# ESP32_Module.net
KiCad netlist of a schematic drawn in Altium Designer
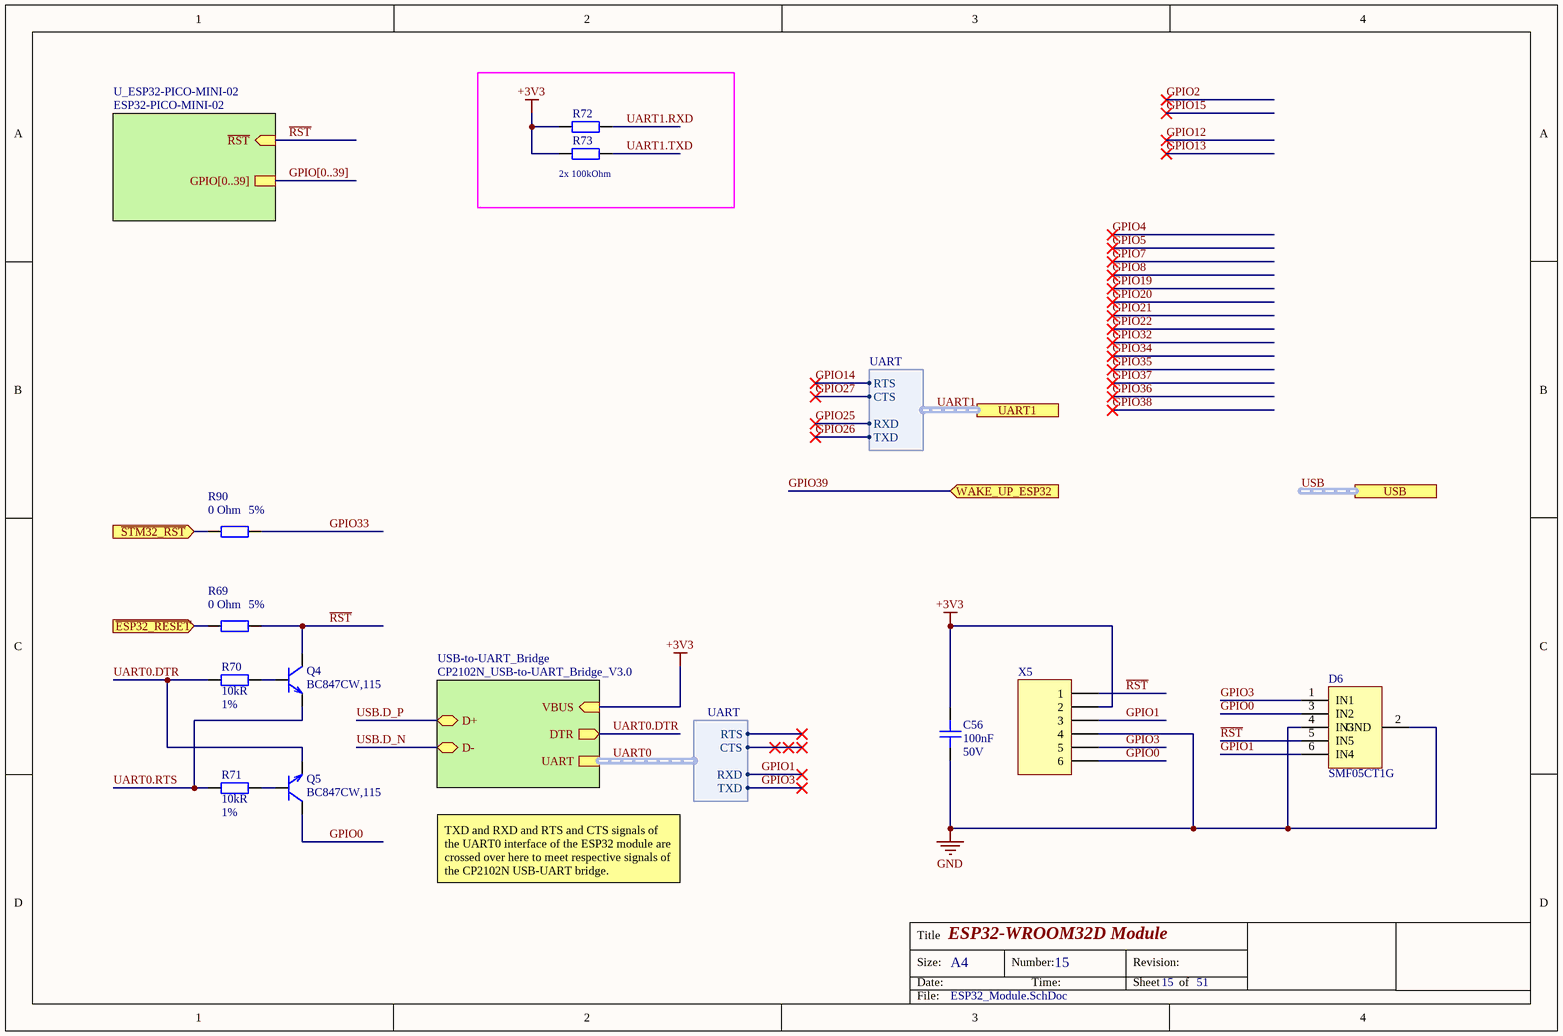
[diagram p0: ESP32_Module.SchDoc]

(export (version "E")
  (design (tool "Eeschema 10.0.6"))
  (components
    (comp (ref "C56")
      (value "CAP CER 0.1UF 50V X7R 0402")
      (footprint "C0402")
      (description "0.1µF ±10% 50V Ceramic Capacitor X7R 0402 (1005 Metric)")
      (fields
        (field (name "MANUFACTURER") "TDK")
        (field (name "MANUFACTURER PART NUMBER") "CGA2B3X7R1H104K050BB")
        (field (name "CAPACITANCE") "100nF")
        (field (name "VOLTAGE") "50V")
      )
      (libsource (lib "capacitors_smd") (part "CAP CER 0.1UF 50V X7R 0402"))
    )
    (comp (ref "D6")
      (value "SMF05CT1G")
      (footprint "SOT363_SOP65P210X265-6N")
      (description "12.5V Clamp 8A (8/20µs) Ipp Tvs Diode Surface Mount SC-88/SC70-6/SOT-363")
      (fields (field (name "MANUFACTURER") "ON Semiconductor"))
      (libsource (lib "diodes_tvs") (part "TVS DIODE 5V 12.5V 5CH SC88"))
    )
    (comp (ref "Q4")
      (value "BC847CW,115")
      (footprint "SOT-323")
      (description "Bipolar (BJT) Transistor NPN 45V 100mA 100MHz 200mW Surface Mount SOT-323-3")
      (fields (field (name "MANUFACTURER") "Nexperia"))
      (libsource (lib "bipolar-junction_transistors") (part "TRANS BC847CW,115 NPN 45V 0.1A SOT323"))
    )
    (comp (ref "Q5")
      (value "BC847CW,115")
      (footprint "SOT-323")
      (description "Bipolar (BJT) Transistor NPN 45V 100mA 100MHz 200mW Surface Mount SOT-323-3")
      (fields (field (name "MANUFACTURER") "Nexperia"))
      (libsource (lib "bipolar-junction_transistors") (part "TRANS BC847CW,115 NPN 45V 0.1A SOT323"))
    )
    (comp (ref "R69")
      (value "RES SMD 0 OHM JUMPER 1/16W 0402")
      (footprint "R0402")
      (description "0 Ohms Jumper 0.063W, 1/16W Chip Resistor 0402 (1005 Metric) Moisture Resistant Thick Film")
      (fields
        (field (name "MANUFACTURER") "Yageo")
        (field (name "MANUFACTURER PART NUMBER") "RC0402JR-070RL")
        (field (name "TOLERANCE") "5%")
        (field (name "RESISTANCE") "0 Ohm")
      )
      (libsource (lib "resistors_smd") (part "RES SMD 0 OHM JUMPER 1/16W 0402"))
    )
    (comp (ref "R70")
      (value "RES SMD 10K OHM 1% 1/16W 0402")
      (footprint "R0402")
      (description "10 kOhms ±1% 0.063W, 1/16W Chip Resistor 0402 (1005 Metric) Moisture Resistant Thick Film")
      (fields
        (field (name "MANUFACTURER PART NUMBER") "RC0402FR-0710KP")
        (field (name "MANUFACTURER") "Yageo")
        (field (name "RESISTANCE") "10kR")
        (field (name "TOLERANCE") "1%")
      )
      (libsource (lib "resistors_smd") (part "RES SMD 10K OHM 1% 1/16W 0402"))
    )
    (comp (ref "R71")
      (value "RES SMD 10K OHM 1% 1/16W 0402")
      (footprint "R0402")
      (description "10 kOhms ±1% 0.063W, 1/16W Chip Resistor 0402 (1005 Metric) Moisture Resistant Thick Film")
      (fields
        (field (name "MANUFACTURER PART NUMBER") "RC0402FR-0710KP")
        (field (name "MANUFACTURER") "Yageo")
        (field (name "RESISTANCE") "10kR")
        (field (name "TOLERANCE") "1%")
      )
      (libsource (lib "resistors_smd") (part "RES SMD 10K OHM 1% 1/16W 0402"))
    )
    (comp (ref "R72")
      (value "RES SMD 100K OHM 1% 1/16W 0402")
      (footprint "R0402")
      (description "100 kOhms ±1% 0.063W, 1/16W Chip Resistor 0402 (1005 Metric) Moisture Resistant Thick Film")
      (fields
        (field (name "MANUFACTURER") "Yageo")
        (field (name "MANUFACTURER PART NUMBER") "RC0402FR-07100KL")
      )
      (libsource (lib "resistors_smd") (part "RES SMD 100K OHM 1% 1/16W 0402"))
    )
    (comp (ref "R73")
      (value "RES SMD 100K OHM 1% 1/16W 0402")
      (footprint "R0402")
      (description "100 kOhms ±1% 0.063W, 1/16W Chip Resistor 0402 (1005 Metric) Moisture Resistant Thick Film")
      (fields
        (field (name "MANUFACTURER") "Yageo")
        (field (name "MANUFACTURER PART NUMBER") "RC0402FR-07100KL")
      )
      (libsource (lib "resistors_smd") (part "RES SMD 100K OHM 1% 1/16W 0402"))
    )
    (comp (ref "R90")
      (value "RES SMD 0 OHM JUMPER 1/16W 0402")
      (footprint "R0402")
      (description "0 Ohms Jumper 0.063W, 1/16W Chip Resistor 0402 (1005 Metric) Moisture Resistant Thick Film")
      (fields
        (field (name "MANUFACTURER") "Yageo")
        (field (name "MANUFACTURER PART NUMBER") "RC0402JR-070RL")
        (field (name "TOLERANCE") "5%")
        (field (name "RESISTANCE") "0 Ohm")
      )
      (libsource (lib "resistors_smd") (part "RES SMD 0 OHM JUMPER 1/16W 0402"))
    )
    (comp (ref "X5")
      (value "~")
      (footprint "TC2030-IDC-NL")
      (description "Tag-Connect TC2030-MCP-NL (3x2 pins No Legs)")
      (fields
        (field (name "MANUFACTURER") "Tag-Connect LLC")
        (field (name "MANUFACTURER PART NUMBER") "TC2030-IDC-NL")
      )
      (libsource (lib "EvansWerks") (part "TC2030-IDC-NL"))
    )
  )
  (nets
    (net (code "17") (name "+3V3") (class "Default")
      (node (ref "C56") (pin "2") (pinfunction "2_2") (pintype "passive"))
      (node (ref "R72") (pin "1") (pinfunction "1_1") (pintype "passive"))
      (node (ref "R73") (pin "1") (pinfunction "1_1") (pintype "passive"))
      (node (ref "X5") (pin "2") (pinfunction "2_2") (pintype "passive"))
    )
    (net (code "18") (name "/ESP32_RESET") (class "Default")
      (node (ref "R69") (pin "1") (pinfunction "1_1") (pintype "passive"))
    )
    (net (code "19") (name "/GPIO0") (class "Default")
      (node (ref "D6") (pin "3") (pinfunction "IN2_3") (pintype "passive"))
      (node (ref "Q5") (pin "3") (pinfunction "C_3") (pintype "passive"))
      (node (ref "X5") (pin "6") (pinfunction "6_6") (pintype "passive"))
    )
    (net (code "20") (name "/GPIO1") (class "Default")
      (node (ref "D6") (pin "6") (pinfunction "IN4_6") (pintype "passive"))
      (node (ref "X5") (pin "3") (pinfunction "3_3") (pintype "passive"))
    )
    (net (code "22") (name "/GPIO3") (class "Default")
      (node (ref "D6") (pin "1") (pinfunction "IN1_1") (pintype "passive"))
      (node (ref "X5") (pin "5") (pinfunction "5_5") (pintype "passive"))
    )
    (net (code "39") (name "/GPIO33") (class "Default")
      (node (ref "R90") (pin "2") (pinfunction "2_2") (pintype "passive"))
    )
    (net (code "47") (name "/RST") (class "Default")
      (node (ref "D6") (pin "5") (pinfunction "IN5_5") (pintype "passive"))
      (node (ref "Q4") (pin "3") (pinfunction "C_3") (pintype "passive"))
      (node (ref "R69") (pin "2") (pinfunction "2_2") (pintype "passive"))
      (node (ref "X5") (pin "1") (pinfunction "1_1") (pintype "passive"))
    )
    (net (code "48") (name "/STM32_RST") (class "Default")
      (node (ref "R90") (pin "1") (pinfunction "1_1") (pintype "passive"))
    )
    (net (code "49") (name "/UART0.DTR") (class "Default")
      (node (ref "Q5") (pin "2") (pinfunction "E_2") (pintype "passive"))
      (node (ref "R70") (pin "1") (pinfunction "1_1") (pintype "passive"))
    )
    (net (code "50") (name "/UART0.RTS") (class "Default")
      (node (ref "Q4") (pin "2") (pinfunction "E_2") (pintype "passive"))
      (node (ref "R71") (pin "1") (pinfunction "1_1") (pintype "passive"))
    )
    (net (code "52") (name "/UART1.RXD") (class "Default")
      (node (ref "R72") (pin "2") (pinfunction "2_2") (pintype "passive"))
    )
    (net (code "53") (name "/UART1.TXD") (class "Default")
      (node (ref "R73") (pin "2") (pinfunction "2_2") (pintype "passive"))
    )
    (net (code "58") (name "GND") (class "Default")
      (node (ref "C56") (pin "1") (pinfunction "1_1") (pintype "passive"))
      (node (ref "D6") (pin "2") (pinfunction "GND_2") (pintype "power_in"))
      (node (ref "D6") (pin "4") (pinfunction "IN3_4") (pintype "passive"))
      (node (ref "X5") (pin "4") (pinfunction "4_4") (pintype "passive"))
    )
    (net (code "59") (name "Net-(Q4-B)") (class "Default")
      (node (ref "Q4") (pin "1") (pinfunction "B_1") (pintype "passive"))
      (node (ref "R70") (pin "2") (pinfunction "2_2") (pintype "passive"))
    )
    (net (code "60") (name "Net-(Q5-B)") (class "Default")
      (node (ref "Q5") (pin "1") (pinfunction "B_1") (pintype "passive"))
      (node (ref "R71") (pin "2") (pinfunction "2_2") (pintype "passive"))
    )
  )
)
